# RF_main_board.net
KiCad netlist of a schematic drawn in Altium Designer
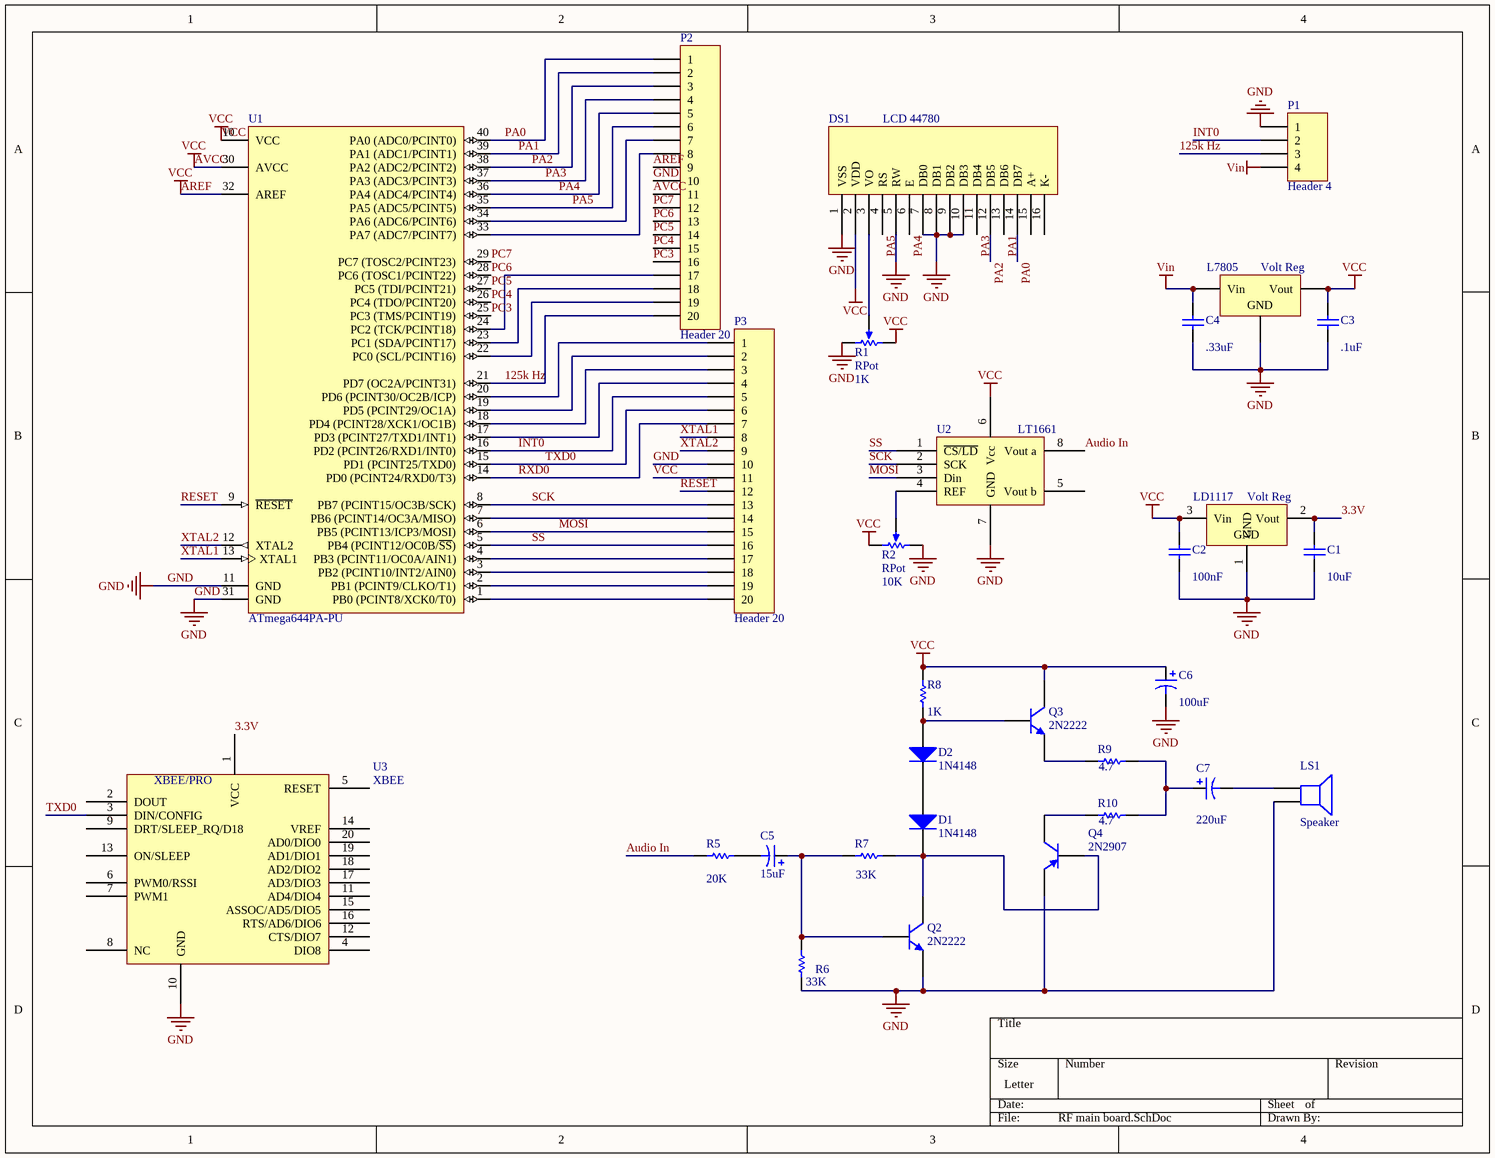
[diagram p0: RF main board.SchDoc]

(export (version "E")
  (design (tool "Eeschema 10.0.6"))
  (components
    (comp (ref "C1")
      (value "10uF")
      (footprint "RAD-0.3")
      (description "Capacitor")
      (fields (field (name "PUBLISHER") "Altium Limited"))
      (libsource (lib "Miscellaneous Devices") (part "Cap"))
    )
    (comp (ref "C2")
      (value "100nF")
      (footprint "RAD-0.3")
      (description "Capacitor")
      (fields (field (name "Comment") "Cap") (field (name "PUBLISHER") "Altium Limited"))
      (libsource (lib "Miscellaneous Devices") (part "Cap"))
    )
    (comp (ref "C3")
      (value ".1uF")
      (footprint "RAD-0.3")
      (description "Capacitor")
      (fields (field (name "Comment") "Cap") (field (name "PUBLISHER") "Altium Limited"))
      (libsource (lib "Miscellaneous Devices") (part "Cap"))
    )
    (comp (ref "C4")
      (value ".33uF")
      (footprint "RAD-0.3")
      (description "Capacitor")
      (fields (field (name "Comment") "Cap") (field (name "PUBLISHER") "Altium Limited"))
      (libsource (lib "Miscellaneous Devices") (part "Cap"))
    )
    (comp (ref "C5")
      (value "15uF")
      (footprint "CAPR5-4X5")
      (description "Polarized Capacitor (Radial)")
      (fields (field (name "Comment") "Cap Pol1") (field (name "PUBLISHER") "Altium Limited"))
      (libsource (lib "Miscellaneous Devices") (part "Cap Pol1"))
    )
    (comp (ref "C6")
      (value "100uF")
      (footprint "CAPR5-4X5")
      (description "Polarized Capacitor (Radial)")
      (fields (field (name "Comment") "Cap Pol1") (field (name "PUBLISHER") "Altium Limited"))
      (libsource (lib "Miscellaneous Devices") (part "Cap Pol1"))
    )
    (comp (ref "C7")
      (value "220uF")
      (footprint "CAPR5-4X5")
      (description "Polarized Capacitor (Radial)")
      (fields (field (name "Comment") "Cap Pol1") (field (name "PUBLISHER") "Altium Limited"))
      (libsource (lib "Miscellaneous Devices") (part "Cap Pol1"))
    )
    (comp (ref "D1")
      (value "1N4148")
      (footprint "DO-35")
      (description "High Conductance Fast Diode")
      (fields (field (name "PUBLISHER") "Altium Limited"))
      (libsource (lib "Miscellaneous Devices") (part "Diode 1N4148"))
    )
    (comp (ref "D2")
      (value "1N4148")
      (footprint "DO-35")
      (description "High Conductance Fast Diode")
      (fields (field (name "PUBLISHER") "Altium Limited"))
      (libsource (lib "Miscellaneous Devices") (part "Diode 1N4148"))
    )
    (comp (ref "DS1")
      (value "LCD 44780")
      (footprint "OLED 16x2")
      (libsource (lib "ECE LIB new") (part "LCD 44780"))
    )
    (comp (ref "L7805")
      (value "Volt Reg")
      (footprint "HDR1X3")
      (description "Voltage Regulator")
      (fields (field (name "PUBLISHER") "Altium Limited"))
      (libsource (lib "") (part "Volt Reg_1"))
    )
    (comp (ref "LD1117")
      (value "Volt Reg")
      (footprint "HDR1X3")
      (description "Voltage Regulator")
      (fields (field (name "PUBLISHER") "Altium Limited"))
      (libsource (lib "Miscellaneous Devices") (part "Volt Reg"))
    )
    (comp (ref "LS1")
      (value "Speaker")
      (footprint "PIN2")
      (description "Loudspeaker")
      (fields (field (name "PUBLISHER") "Altium Limited"))
      (libsource (lib "Miscellaneous Devices") (part "Speaker"))
    )
    (comp (ref "P1")
      (value "Header 4")
      (footprint "HDR1X4")
      (description "Header, 4-Pin")
      (fields (field (name "PUBLISHER") "Altium Limited"))
      (libsource (lib "Miscellaneous Connectors") (part "Header 4"))
    )
    (comp (ref "P2")
      (value "Header 20")
      (footprint "HDR1X20")
      (description "Header, 20-Pin")
      (fields (field (name "PUBLISHER") "Altium Limited"))
      (libsource (lib "Miscellaneous Connectors") (part "Header 20"))
    )
    (comp (ref "P3")
      (value "Header 20")
      (footprint "HDR1X20")
      (description "Header, 20-Pin")
      (fields (field (name "PUBLISHER") "Altium Limited"))
      (libsource (lib "Miscellaneous Connectors") (part "Header 20"))
    )
    (comp (ref "Q2")
      (value "2N2222")
      (footprint "TO-226-AA")
      (description "NPN Bipolar Transistor")
      (fields (field (name "PUBLISHER") "Altium Limited"))
      (libsource (lib "Miscellaneous Devices") (part "NPN"))
    )
    (comp (ref "Q3")
      (value "2N2222")
      (footprint "TO-226-AA")
      (description "NPN Bipolar Transistor")
      (fields (field (name "PUBLISHER") "Altium Limited"))
      (libsource (lib "Miscellaneous Devices") (part "NPN"))
    )
    (comp (ref "Q4")
      (value "2N2907")
      (footprint "TO-226-AA")
      (description "PNP Bipolar Transistor")
      (fields (field (name "PUBLISHER") "Altium Limited"))
      (libsource (lib "Miscellaneous Devices") (part "PNP"))
    )
    (comp (ref "R1")
      (value "RPot")
      (footprint "VR5")
      (description "Potentiometer")
      (fields (field (name "ALTIUM_VALUE") "1K") (field (name "PUBLISHER") "Altium Limited"))
      (libsource (lib "Miscellaneous Devices") (part "RPot"))
    )
    (comp (ref "R2")
      (value "RPot")
      (footprint "VR5")
      (description "Potentiometer")
      (fields (field (name "ALTIUM_VALUE") "10K") (field (name "PUBLISHER") "Altium Limited"))
      (libsource (lib "Miscellaneous Devices") (part "RPot"))
    )
    (comp (ref "R5")
      (value "20K")
      (footprint "AXIAL-0.3")
      (description "Resistor")
      (fields (field (name "Comment") "Res1") (field (name "PUBLISHER") "Altium Limited"))
      (libsource (lib "Miscellaneous Devices") (part "Res1"))
    )
    (comp (ref "R6")
      (value "33K")
      (footprint "AXIAL-0.3")
      (description "Resistor")
      (fields (field (name "Comment") "Res1") (field (name "PUBLISHER") "Altium Limited"))
      (libsource (lib "Miscellaneous Devices") (part "Res1"))
    )
    (comp (ref "R7")
      (value "33K")
      (footprint "AXIAL-0.3")
      (description "Resistor")
      (fields (field (name "Comment") "Res1") (field (name "PUBLISHER") "Altium Limited"))
      (libsource (lib "Miscellaneous Devices") (part "Res1"))
    )
    (comp (ref "R8")
      (value "1K")
      (footprint "AXIAL-0.3")
      (description "Resistor")
      (fields (field (name "Comment") "Res1") (field (name "PUBLISHER") "Altium Limited"))
      (libsource (lib "Miscellaneous Devices") (part "Res1"))
    )
    (comp (ref "R9")
      (value "4.7")
      (footprint "AXIAL-0.3")
      (description "Resistor")
      (fields (field (name "Comment") "Res1") (field (name "PUBLISHER") "Altium Limited"))
      (libsource (lib "Miscellaneous Devices") (part "Res1"))
    )
    (comp (ref "R10")
      (value "4.7")
      (footprint "AXIAL-0.3")
      (description "Resistor")
      (fields (field (name "PUBLISHER") "Altium Limited"))
      (libsource (lib "Miscellaneous Devices") (part "Res1"))
    )
    (comp (ref "U1")
      (value "ATmega644PA-PU")
      (footprint "40P6")
      (libsource (lib "Atmel Microcontroller megaAVR") (part "ATmega644PA-PU"))
    )
    (comp (ref "U2") (value "LT1661") (footprint "DIP-8") (libsource (lib "ECE LIB new") (part "LT1661")))
    (comp (ref "U3") (value "XBEE") (footprint "XBEE/PRO") (libsource (lib "ECE LIB new") (part "XBEE")))
  )
  (nets
    (net (code "1") (name "/3.3V") (class "Default")
      (node (ref "C1") (pin "2") (pinfunction "2_2") (pintype "passive"))
      (node (ref "LD1117") (pin "2") (pinfunction "Vout_2") (pintype "passive"))
      (node (ref "U3") (pin "1") (pinfunction "VCC_1") (pintype "passive"))
    )
    (net (code "2") (name "/125k Hz") (class "Default")
      (node (ref "P1") (pin "3") (pinfunction "3_3") (pintype "passive"))
      (node (ref "P2") (pin "20") (pinfunction "20_20") (pintype "passive"))
      (node (ref "U1") (pin "21") (pinfunction "PD7_(OC2A/PCINT31)_21") (pintype "bidirectional"))
    )
    (net (code "3") (name "/Audio In") (class "Default")
      (node (ref "R5") (pin "1") (pinfunction "1_1") (pintype "passive"))
      (node (ref "U2") (pin "8") (pinfunction "Vout_a_8") (pintype "passive"))
    )
    (net (code "4") (name "/INT0") (class "Default")
      (node (ref "P1") (pin "2") (pinfunction "2_2") (pintype "passive"))
      (node (ref "P3") (pin "5") (pinfunction "5_5") (pintype "passive"))
      (node (ref "U1") (pin "16") (pinfunction "PD2_(PCINT26/RXD1/INT0)_16") (pintype "bidirectional"))
    )
    (net (code "5") (name "/MOSI") (class "Default")
      (node (ref "P3") (pin "15") (pinfunction "15_15") (pintype "passive"))
      (node (ref "U1") (pin "6") (pinfunction "PB5_(PCINT13/ICP3/MOSI)_6") (pintype "bidirectional"))
      (node (ref "U2") (pin "3") (pinfunction "Din_3") (pintype "passive"))
    )
    (net (code "6") (name "/PA0") (class "Default")
      (node (ref "DS1") (pin "14") (pinfunction "DB7_14") (pintype "passive"))
      (node (ref "P2") (pin "1") (pinfunction "1_1") (pintype "passive"))
      (node (ref "U1") (pin "40") (pinfunction "PA0_(ADC0/PCINT0)_40") (pintype "bidirectional"))
    )
    (net (code "7") (name "/PA1") (class "Default")
      (node (ref "DS1") (pin "13") (pinfunction "DB6_13") (pintype "passive"))
      (node (ref "P2") (pin "2") (pinfunction "2_2") (pintype "passive"))
      (node (ref "U1") (pin "39") (pinfunction "PA1_(ADC1/PCINT1)_39") (pintype "bidirectional"))
    )
    (net (code "8") (name "/PA2") (class "Default")
      (node (ref "DS1") (pin "12") (pinfunction "DB5_12") (pintype "passive"))
      (node (ref "P2") (pin "3") (pinfunction "3_3") (pintype "passive"))
      (node (ref "U1") (pin "38") (pinfunction "PA2_(ADC2/PCINT2)_38") (pintype "bidirectional"))
    )
    (net (code "9") (name "/PA3") (class "Default")
      (node (ref "DS1") (pin "11") (pinfunction "DB4_11") (pintype "passive"))
      (node (ref "P2") (pin "4") (pinfunction "4_4") (pintype "passive"))
      (node (ref "U1") (pin "37") (pinfunction "PA3_(ADC3/PCINT3)_37") (pintype "bidirectional"))
    )
    (net (code "10") (name "/PA4") (class "Default")
      (node (ref "DS1") (pin "6") (pinfunction "E_6") (pintype "passive"))
      (node (ref "P2") (pin "5") (pinfunction "5_5") (pintype "passive"))
      (node (ref "U1") (pin "36") (pinfunction "PA4_(ADC4/PCINT4)_36") (pintype "bidirectional"))
    )
    (net (code "11") (name "/PA5") (class "Default")
      (node (ref "DS1") (pin "4") (pinfunction "RS_4") (pintype "passive"))
      (node (ref "P2") (pin "6") (pinfunction "6_6") (pintype "passive"))
      (node (ref "U1") (pin "35") (pinfunction "PA5_(ADC5/PCINT5)_35") (pintype "bidirectional"))
    )
    (net (code "12") (name "/PC3") (class "Default")
      (node (ref "P2") (pin "16") (pinfunction "16_16") (pintype "passive"))
      (node (ref "U1") (pin "25") (pinfunction "PC3_(TMS/PCINT19)_25") (pintype "bidirectional"))
    )
    (net (code "13") (name "/PC4") (class "Default")
      (node (ref "P2") (pin "15") (pinfunction "15_15") (pintype "passive"))
      (node (ref "U1") (pin "26") (pinfunction "PC4_(TDO/PCINT20)_26") (pintype "bidirectional"))
    )
    (net (code "14") (name "/PC5") (class "Default")
      (node (ref "P2") (pin "14") (pinfunction "14_14") (pintype "passive"))
      (node (ref "U1") (pin "27") (pinfunction "PC5_(TDI/PCINT21)_27") (pintype "bidirectional"))
    )
    (net (code "15") (name "/PC6") (class "Default")
      (node (ref "P2") (pin "13") (pinfunction "13_13") (pintype "passive"))
      (node (ref "U1") (pin "28") (pinfunction "PC6_(TOSC1/PCINT22)_28") (pintype "bidirectional"))
    )
    (net (code "16") (name "/PC7") (class "Default")
      (node (ref "P2") (pin "12") (pinfunction "12_12") (pintype "passive"))
      (node (ref "U1") (pin "29") (pinfunction "PC7_(TOSC2/PCINT23)_29") (pintype "bidirectional"))
    )
    (net (code "17") (name "/RESET") (class "Default")
      (node (ref "P3") (pin "12") (pinfunction "12_12") (pintype "passive"))
      (node (ref "U1") (pin "9") (pinfunction "~{RESET}_9") (pintype "input"))
    )
    (net (code "18") (name "/RXD0") (class "Default")
      (node (ref "P3") (pin "7") (pinfunction "7_7") (pintype "passive"))
      (node (ref "U1") (pin "14") (pinfunction "PD0_(PCINT24/RXD0/T3)_14") (pintype "bidirectional"))
    )
    (net (code "19") (name "/SCK") (class "Default")
      (node (ref "P3") (pin "13") (pinfunction "13_13") (pintype "passive"))
      (node (ref "U1") (pin "8") (pinfunction "PB7_(PCINT15/OC3B/SCK)_8") (pintype "bidirectional"))
      (node (ref "U2") (pin "2") (pinfunction "SCK_2") (pintype "passive"))
    )
    (net (code "20") (name "/SS") (class "Default")
      (node (ref "P3") (pin "16") (pinfunction "16_16") (pintype "passive"))
      (node (ref "U1") (pin "5") (pinfunction "PB4_(PCINT12/OC0B/~{SS})_5") (pintype "bidirectional"))
      (node (ref "U2") (pin "1") (pinfunction "~{CS/LD}_1") (pintype "passive"))
    )
    (net (code "21") (name "/TXD0") (class "Default")
      (node (ref "P3") (pin "6") (pinfunction "6_6") (pintype "passive"))
      (node (ref "U1") (pin "15") (pinfunction "PD1_(PCINT25/TXD0)_15") (pintype "bidirectional"))
      (node (ref "U3") (pin "3") (pinfunction "DIN/CONFIG_3") (pintype "passive"))
    )
    (net (code "22") (name "/XTAL1") (class "Default")
      (node (ref "P3") (pin "8") (pinfunction "8_8") (pintype "passive"))
      (node (ref "U1") (pin "13") (pinfunction "XTAL1_13") (pintype "input"))
    )
    (net (code "23") (name "/XTAL2") (class "Default")
      (node (ref "P3") (pin "9") (pinfunction "9_9") (pintype "passive"))
      (node (ref "U1") (pin "12") (pinfunction "XTAL2_12") (pintype "output"))
    )
    (net (code "24") (name "GND") (class "Default")
      (node (ref "C1") (pin "1") (pinfunction "1_1") (pintype "passive"))
      (node (ref "C2") (pin "1") (pinfunction "1_1") (pintype "passive"))
      (node (ref "C3") (pin "1") (pinfunction "1_1") (pintype "passive"))
      (node (ref "C4") (pin "1") (pinfunction "1_1") (pintype "passive"))
      (node (ref "C6") (pin "2") (pinfunction "2_2") (pintype "passive"))
      (node (ref "DS1") (pin "1") (pinfunction "VSS_1") (pintype "passive"))
      (node (ref "DS1") (pin "10") (pinfunction "DB3_10") (pintype "passive"))
      (node (ref "DS1") (pin "5") (pinfunction "RW_5") (pintype "passive"))
      (node (ref "DS1") (pin "7") (pinfunction "DB0_7") (pintype "passive"))
      (node (ref "DS1") (pin "8") (pinfunction "DB1_8") (pintype "passive"))
      (node (ref "DS1") (pin "9") (pinfunction "DB2_9") (pintype "passive"))
      (node (ref "L7805") (pin "2") (pinfunction "GND_2") (pintype "passive"))
      (node (ref "LD1117") (pin "1") (pinfunction "GND_1") (pintype "passive"))
      (node (ref "LS1") (pin "2") (pinfunction "2_2") (pintype "passive"))
      (node (ref "P1") (pin "1") (pinfunction "1_1") (pintype "passive"))
      (node (ref "P2") (pin "10") (pinfunction "10_10") (pintype "passive"))
      (node (ref "P3") (pin "10") (pinfunction "10_10") (pintype "passive"))
      (node (ref "Q2") (pin "3") (pinfunction "E_3") (pintype "passive"))
      (node (ref "Q4") (pin "3") (pinfunction "E_3") (pintype "passive"))
      (node (ref "R1") (pin "2") (pinfunction "BOT_2") (pintype "passive"))
      (node (ref "R2") (pin "1") (pinfunction "TOP_1") (pintype "passive"))
      (node (ref "R6") (pin "2") (pinfunction "2_2") (pintype "passive"))
      (node (ref "U1") (pin "11") (pinfunction "GND_11") (pintype "power_in"))
      (node (ref "U1") (pin "31") (pinfunction "GND_31") (pintype "power_in"))
      (node (ref "U2") (pin "7") (pinfunction "GND_7") (pintype "passive"))
      (node (ref "U3") (pin "10") (pinfunction "GND_10") (pintype "passive"))
    )
    (net (code "25") (name "Net-(C5-Pad2)") (class "Default")
      (node (ref "C5") (pin "2") (pinfunction "2_2") (pintype "passive"))
      (node (ref "R5") (pin "2") (pinfunction "2_2") (pintype "passive"))
    )
    (net (code "26") (name "Net-(C7-Pad1)") (class "Default")
      (node (ref "C7") (pin "1") (pinfunction "1_1") (pintype "passive"))
      (node (ref "R10") (pin "2") (pinfunction "2_2") (pintype "passive"))
      (node (ref "R9") (pin "2") (pinfunction "2_2") (pintype "passive"))
    )
    (net (code "27") (name "Net-(C7-Pad2)") (class "Default")
      (node (ref "C7") (pin "2") (pinfunction "2_2") (pintype "passive"))
      (node (ref "LS1") (pin "1") (pinfunction "1_1") (pintype "passive"))
    )
    (net (code "28") (name "Net-(D1-A)") (class "Default")
      (node (ref "D1") (pin "1") (pinfunction "A_1") (pintype "passive"))
      (node (ref "D2") (pin "2") (pinfunction "K_2") (pintype "passive"))
    )
    (net (code "29") (name "Net-(D1-K)") (class "Default")
      (node (ref "D1") (pin "2") (pinfunction "K_2") (pintype "passive"))
      (node (ref "Q2") (pin "1") (pinfunction "C_1") (pintype "passive"))
      (node (ref "Q4") (pin "2") (pinfunction "B_2") (pintype "passive"))
      (node (ref "R7") (pin "1") (pinfunction "1_1") (pintype "passive"))
    )
    (net (code "30") (name "Net-(D2-A)") (class "Default")
      (node (ref "D2") (pin "1") (pinfunction "A_1") (pintype "passive"))
      (node (ref "Q3") (pin "2") (pinfunction "B_2") (pintype "passive"))
      (node (ref "R8") (pin "1") (pinfunction "1_1") (pintype "passive"))
    )
    (net (code "31") (name "Net-(DS1-VO)") (class "Default")
      (node (ref "DS1") (pin "3") (pinfunction "VO_3") (pintype "passive"))
      (node (ref "R1") (pin "3") (pinfunction "TAP_3") (pintype "passive"))
    )
    (net (code "32") (name "Net-(Q2-B)") (class "Default")
      (node (ref "C5") (pin "1") (pinfunction "1_1") (pintype "passive"))
      (node (ref "Q2") (pin "2") (pinfunction "B_2") (pintype "passive"))
      (node (ref "R6") (pin "1") (pinfunction "1_1") (pintype "passive"))
      (node (ref "R7") (pin "2") (pinfunction "2_2") (pintype "passive"))
    )
    (net (code "33") (name "Net-(Q3-E)") (class "Default")
      (node (ref "Q3") (pin "3") (pinfunction "E_3") (pintype "passive"))
      (node (ref "R9") (pin "1") (pinfunction "1_1") (pintype "passive"))
    )
    (net (code "34") (name "Net-(Q4-C)") (class "Default")
      (node (ref "Q4") (pin "1") (pinfunction "C_1") (pintype "passive"))
      (node (ref "R10") (pin "1") (pinfunction "1_1") (pintype "passive"))
    )
    (net (code "35") (name "Net-(R2-TAP)") (class "Default")
      (node (ref "R2") (pin "3") (pinfunction "TAP_3") (pintype "passive"))
      (node (ref "U2") (pin "4") (pinfunction "REF_4") (pintype "passive"))
    )
    (net (code "36") (name "Net-(U1-PA6_(ADC6{slash}PCINT6))") (class "Default")
      (node (ref "P2") (pin "7") (pinfunction "7_7") (pintype "passive"))
      (node (ref "U1") (pin "34") (pinfunction "PA6_(ADC6/PCINT6)_34") (pintype "bidirectional"))
    )
    (net (code "37") (name "Net-(U1-PA7_(ADC7{slash}PCINT7))") (class "Default")
      (node (ref "P2") (pin "8") (pinfunction "8_8") (pintype "passive"))
      (node (ref "U1") (pin "33") (pinfunction "PA7_(ADC7/PCINT7)_33") (pintype "bidirectional"))
    )
    (net (code "38") (name "Net-(U1-PB0_(PCINT8{slash}XCK0{slash}T0))") (class "Default")
      (node (ref "P3") (pin "20") (pinfunction "20_20") (pintype "passive"))
      (node (ref "U1") (pin "1") (pinfunction "PB0_(PCINT8/XCK0/T0)_1") (pintype "bidirectional"))
    )
    (net (code "39") (name "Net-(U1-PB1_(PCINT9{slash}CLKO{slash}T1))") (class "Default")
      (node (ref "P3") (pin "19") (pinfunction "19_19") (pintype "passive"))
      (node (ref "U1") (pin "2") (pinfunction "PB1_(PCINT9/CLKO/T1)_2") (pintype "bidirectional"))
    )
    (net (code "40") (name "Net-(U1-PB2_(PCINT10{slash}INT2{slash}AIN0))") (class "Default")
      (node (ref "P3") (pin "18") (pinfunction "18_18") (pintype "passive"))
      (node (ref "U1") (pin "3") (pinfunction "PB2_(PCINT10/INT2/AIN0)_3") (pintype "bidirectional"))
    )
    (net (code "41") (name "Net-(U1-PB3_(PCINT11{slash}OC0A{slash}AIN1))") (class "Default")
      (node (ref "P3") (pin "17") (pinfunction "17_17") (pintype "passive"))
      (node (ref "U1") (pin "4") (pinfunction "PB3_(PCINT11/OC0A/AIN1)_4") (pintype "bidirectional"))
    )
    (net (code "42") (name "Net-(U1-PB6_(PCINT14{slash}OC3A{slash}MISO))") (class "Default")
      (node (ref "P3") (pin "14") (pinfunction "14_14") (pintype "passive"))
      (node (ref "U1") (pin "7") (pinfunction "PB6_(PCINT14/OC3A/MISO)_7") (pintype "bidirectional"))
    )
    (net (code "43") (name "Net-(U1-PC0_(SCL{slash}PCINT16))") (class "Default")
      (node (ref "P2") (pin "19") (pinfunction "19_19") (pintype "passive"))
      (node (ref "U1") (pin "22") (pinfunction "PC0_(SCL/PCINT16)_22") (pintype "bidirectional"))
    )
    (net (code "44") (name "Net-(U1-PC1_(SDA{slash}PCINT17))") (class "Default")
      (node (ref "P2") (pin "18") (pinfunction "18_18") (pintype "passive"))
      (node (ref "U1") (pin "23") (pinfunction "PC1_(SDA/PCINT17)_23") (pintype "bidirectional"))
    )
    (net (code "45") (name "Net-(U1-PC2_(TCK{slash}PCINT18))") (class "Default")
      (node (ref "P2") (pin "17") (pinfunction "17_17") (pintype "passive"))
      (node (ref "U1") (pin "24") (pinfunction "PC2_(TCK/PCINT18)_24") (pintype "bidirectional"))
    )
    (net (code "46") (name "Net-(U1-PD3_(PCINT27{slash}TXD1{slash}INT1))") (class "Default")
      (node (ref "P3") (pin "4") (pinfunction "4_4") (pintype "passive"))
      (node (ref "U1") (pin "17") (pinfunction "PD3_(PCINT27/TXD1/INT1)_17") (pintype "bidirectional"))
    )
    (net (code "47") (name "Net-(U1-PD4_(PCINT28{slash}XCK1{slash}OC1B))") (class "Default")
      (node (ref "P3") (pin "3") (pinfunction "3_3") (pintype "passive"))
      (node (ref "U1") (pin "18") (pinfunction "PD4_(PCINT28/XCK1/OC1B)_18") (pintype "bidirectional"))
    )
    (net (code "48") (name "Net-(U1-PD5_(PCINT29{slash}OC1A))") (class "Default")
      (node (ref "P3") (pin "2") (pinfunction "2_2") (pintype "passive"))
      (node (ref "U1") (pin "19") (pinfunction "PD5_(PCINT29/OC1A)_19") (pintype "bidirectional"))
    )
    (net (code "49") (name "Net-(U1-PD6_(PCINT30{slash}OC2B{slash}ICP))") (class "Default")
      (node (ref "P3") (pin "1") (pinfunction "1_1") (pintype "passive"))
      (node (ref "U1") (pin "20") (pinfunction "PD6_(PCINT30/OC2B/ICP)_20") (pintype "bidirectional"))
    )
    (net (code "50") (name "VCC") (class "Default")
      (node (ref "C2") (pin "2") (pinfunction "2_2") (pintype "passive"))
      (node (ref "C3") (pin "2") (pinfunction "2_2") (pintype "passive"))
      (node (ref "C6") (pin "1") (pinfunction "1_1") (pintype "passive"))
      (node (ref "DS1") (pin "2") (pinfunction "VDD_2") (pintype "passive"))
      (node (ref "L7805") (pin "3") (pinfunction "Vout_3") (pintype "passive"))
      (node (ref "LD1117") (pin "3") (pinfunction "Vin_3") (pintype "passive"))
      (node (ref "P2") (pin "11") (pinfunction "11_11") (pintype "passive"))
      (node (ref "P2") (pin "9") (pinfunction "9_9") (pintype "passive"))
      (node (ref "P3") (pin "11") (pinfunction "11_11") (pintype "passive"))
      (node (ref "Q3") (pin "1") (pinfunction "C_1") (pintype "passive"))
      (node (ref "R1") (pin "1") (pinfunction "TOP_1") (pintype "passive"))
      (node (ref "R2") (pin "2") (pinfunction "BOT_2") (pintype "passive"))
      (node (ref "R8") (pin "2") (pinfunction "2_2") (pintype "passive"))
      (node (ref "U1") (pin "10") (pinfunction "VCC_10") (pintype "power_in"))
      (node (ref "U1") (pin "30") (pinfunction "AVCC_30") (pintype "power_in"))
      (node (ref "U1") (pin "32") (pinfunction "AREF_32") (pintype "power_in"))
      (node (ref "U2") (pin "6") (pinfunction "Vcc_6") (pintype "passive"))
    )
    (net (code "51") (name "Vin") (class "Default")
      (node (ref "C4") (pin "2") (pinfunction "2_2") (pintype "passive"))
      (node (ref "L7805") (pin "1") (pinfunction "Vin_1") (pintype "passive"))
      (node (ref "P1") (pin "4") (pinfunction "4_4") (pintype "passive"))
    )
    (net (code "52") (name "unconnected-(DS1-A+-Pad15)") (class "Default")
      (node (ref "DS1") (pin "15") (pinfunction "A+_15") (pintype "passive"))
    )
    (net (code "53") (name "unconnected-(DS1-K--Pad16)") (class "Default")
      (node (ref "DS1") (pin "16") (pinfunction "K-_16") (pintype "passive"))
    )
    (net (code "54") (name "unconnected-(U2-Vout_b-Pad5)") (class "Default")
      (node (ref "U2") (pin "5") (pinfunction "Vout_b_5") (pintype "passive"))
    )
    (net (code "55") (name "unconnected-(U3-AD0{slash}DIO0-Pad20)") (class "Default")
      (node (ref "U3") (pin "20") (pinfunction "AD0/DIO0_20") (pintype "passive"))
    )
    (net (code "56") (name "unconnected-(U3-AD1{slash}DIO1-Pad19)") (class "Default")
      (node (ref "U3") (pin "19") (pinfunction "AD1/DIO1_19") (pintype "passive"))
    )
    (net (code "57") (name "unconnected-(U3-AD2{slash}DIO2-Pad18)") (class "Default")
      (node (ref "U3") (pin "18") (pinfunction "AD2/DIO2_18") (pintype "passive"))
    )
    (net (code "58") (name "unconnected-(U3-AD3{slash}DIO3-Pad17)") (class "Default")
      (node (ref "U3") (pin "17") (pinfunction "AD3/DIO3_17") (pintype "passive"))
    )
    (net (code "59") (name "unconnected-(U3-AD4{slash}DIO4-Pad11)") (class "Default")
      (node (ref "U3") (pin "11") (pinfunction "AD4/DIO4_11") (pintype "passive"))
    )
    (net (code "60") (name "unconnected-(U3-ASSOC{slash}AD5{slash}DIO5-Pad15)") (class "Default")
      (node (ref "U3") (pin "15") (pinfunction "ASSOC/AD5/DIO5_15") (pintype "passive"))
    )
    (net (code "61") (name "unconnected-(U3-CTS{slash}DIO7-Pad12)") (class "Default")
      (node (ref "U3") (pin "12") (pinfunction "CTS/DIO7_12") (pintype "passive"))
    )
    (net (code "62") (name "unconnected-(U3-DIO8-Pad4)") (class "Default")
      (node (ref "U3") (pin "4") (pinfunction "DIO8_4") (pintype "passive"))
    )
    (net (code "63") (name "unconnected-(U3-DOUT-Pad2)") (class "Default")
      (node (ref "U3") (pin "2") (pinfunction "DOUT_2") (pintype "passive"))
    )
    (net (code "64") (name "unconnected-(U3-DRT{slash}SLEEP_RQ{slash}D18-Pad9)") (class "Default")
      (node (ref "U3") (pin "9") (pinfunction "DRT/SLEEP_RQ/D18_9") (pintype "passive"))
    )
    (net (code "65") (name "unconnected-(U3-NC-Pad8)") (class "Default")
      (node (ref "U3") (pin "8") (pinfunction "NC_8") (pintype "passive"))
    )
    (net (code "66") (name "unconnected-(U3-ON{slash}SLEEP-Pad13)") (class "Default")
      (node (ref "U3") (pin "13") (pinfunction "ON/SLEEP_13") (pintype "passive"))
    )
    (net (code "67") (name "unconnected-(U3-PWM0{slash}RSSI-Pad6)") (class "Default")
      (node (ref "U3") (pin "6") (pinfunction "PWM0/RSSI_6") (pintype "passive"))
    )
    (net (code "68") (name "unconnected-(U3-PWM1-Pad7)") (class "Default")
      (node (ref "U3") (pin "7") (pinfunction "PWM1_7") (pintype "passive"))
    )
    (net (code "69") (name "unconnected-(U3-RESET-Pad5)") (class "Default")
      (node (ref "U3") (pin "5") (pinfunction "RESET_5") (pintype "passive"))
    )
    (net (code "70") (name "unconnected-(U3-RTS{slash}AD6{slash}DIO6-Pad16)") (class "Default")
      (node (ref "U3") (pin "16") (pinfunction "RTS/AD6/DIO6_16") (pintype "passive"))
    )
    (net (code "71") (name "unconnected-(U3-VREF-Pad14)") (class "Default")
      (node (ref "U3") (pin "14") (pinfunction "VREF_14") (pintype "passive"))
    )
  )
)
